# COMS0001_Beacon.net
KiCad netlist of a schematic drawn in Altium Designer
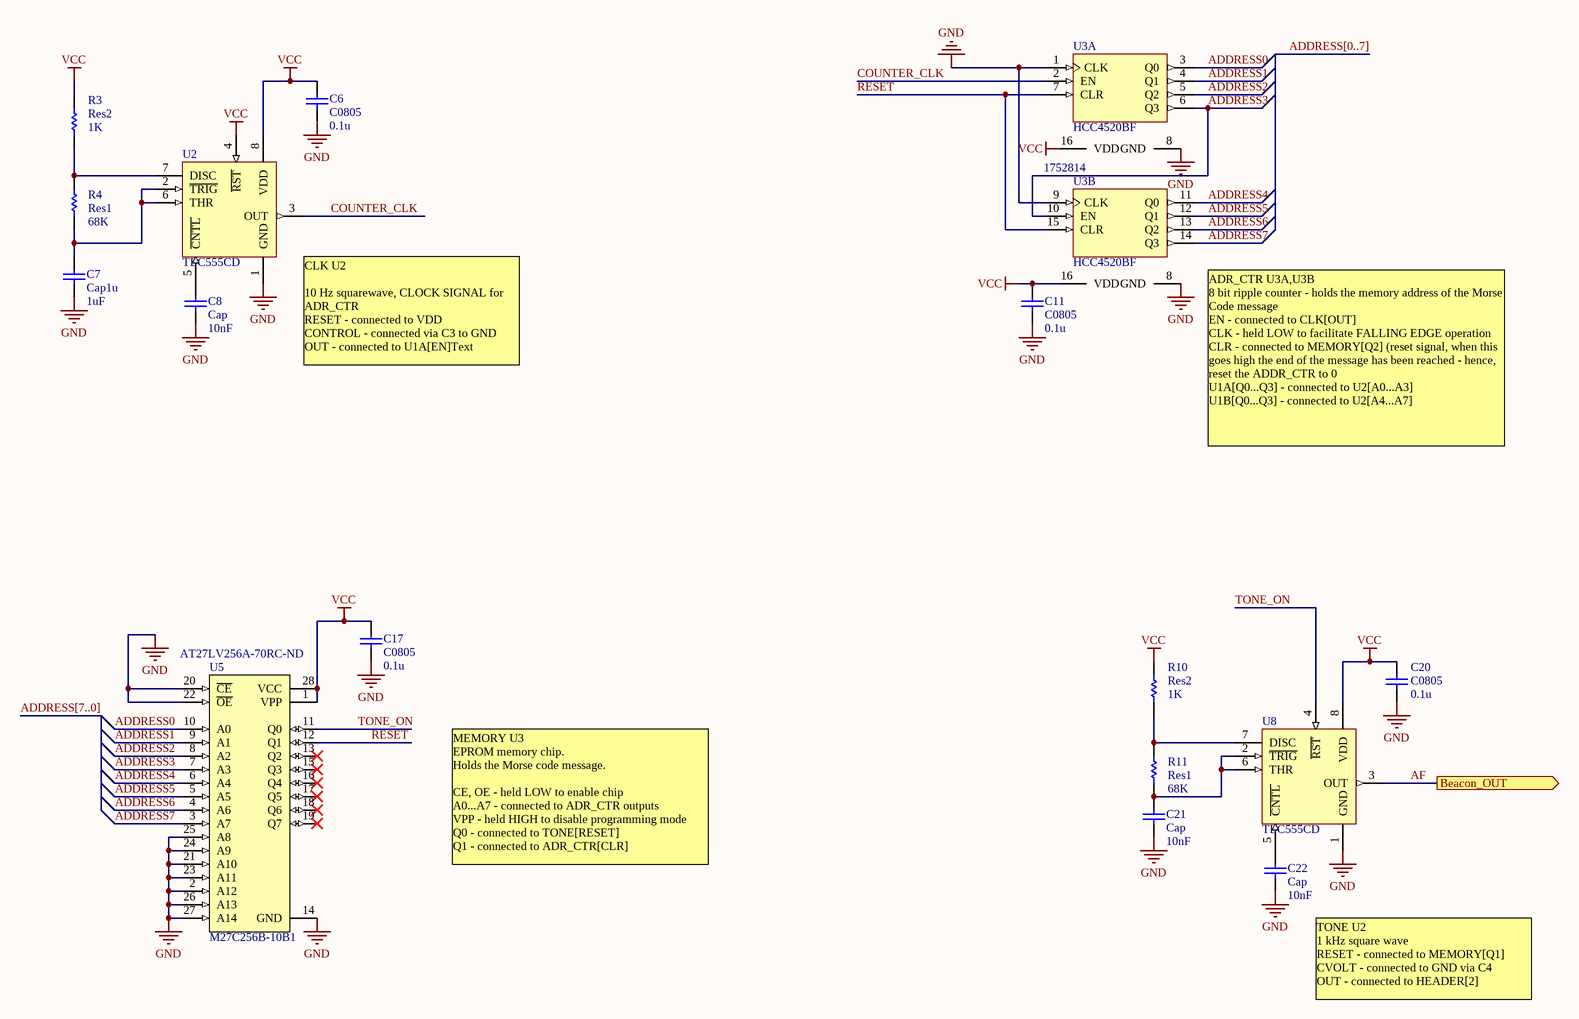
[diagram p0: COMS0001_Beacon.SchDoc]

(export (version "E")
  (design (tool "Eeschema 10.0.6"))
  (components
    (comp (ref "C6")
      (value "C0805")
      (footprint "CAPC2012M")
      (description "Capacitor")
      (fields (field (name "ALTIUM_VALUE") "0.1u") (field (name "PUBLISHER") "Altium Limited"))
      (libsource (lib "Miscellaneous Devices") (part "Cap"))
    )
    (comp (ref "C7")
      (value "Cap1u")
      (footprint "CAPC2012M")
      (description "Capacitor")
      (fields (field (name "ALTIUM_VALUE") "1uF") (field (name "PUBLISHER") "Altium Limited"))
      (libsource (lib "Miscellaneous Devices") (part "Cap"))
    )
    (comp (ref "C8")
      (value "Cap")
      (footprint "CAPC2012M")
      (description "Capacitor")
      (fields (field (name "ALTIUM_VALUE") "10nF") (field (name "PUBLISHER") "Altium Limited"))
      (libsource (lib "Miscellaneous Devices") (part "Cap"))
    )
    (comp (ref "C11")
      (value "C0805")
      (footprint "CAPC2012M")
      (description "Capacitor")
      (fields (field (name "ALTIUM_VALUE") "0.1u") (field (name "PUBLISHER") "Altium Limited"))
      (libsource (lib "Miscellaneous Devices") (part "Cap"))
    )
    (comp (ref "C17")
      (value "C0805")
      (footprint "CAPC2012M")
      (description "Capacitor")
      (fields (field (name "ALTIUM_VALUE") "0.1u") (field (name "PUBLISHER") "Altium Limited"))
      (libsource (lib "Miscellaneous Devices") (part "Cap"))
    )
    (comp (ref "C20")
      (value "C0805")
      (footprint "CAPC2012M")
      (description "Capacitor")
      (fields (field (name "ALTIUM_VALUE") "0.1u") (field (name "PUBLISHER") "Altium Limited"))
      (libsource (lib "Miscellaneous Devices") (part "Cap"))
    )
    (comp (ref "C21")
      (value "Cap")
      (footprint "CAPC2012M")
      (description "Capacitor")
      (fields (field (name "ALTIUM_VALUE") "10nF") (field (name "PUBLISHER") "Altium Limited"))
      (libsource (lib "Miscellaneous Devices") (part "Cap"))
    )
    (comp (ref "C22")
      (value "Cap")
      (footprint "CAPC2012M")
      (description "Capacitor")
      (fields (field (name "ALTIUM_VALUE") "10nF") (field (name "PUBLISHER") "Altium Limited"))
      (libsource (lib "Miscellaneous Devices") (part "Cap"))
    )
    (comp (ref "R3")
      (value "Res2")
      (footprint "RESC2012M")
      (description "Resistor")
      (fields (field (name "ALTIUM_VALUE") "1K") (field (name "PUBLISHER") "Altium Limited"))
      (libsource (lib "Miscellaneous Devices") (part "Res1"))
    )
    (comp (ref "R4")
      (value "Res1")
      (footprint "RESC2012M")
      (description "Resistor")
      (fields (field (name "ALTIUM_VALUE") "68K") (field (name "PUBLISHER") "Altium Limited"))
      (libsource (lib "Miscellaneous Devices") (part "Res1"))
    )
    (comp (ref "R10")
      (value "Res2")
      (footprint "RESC2012M")
      (description "Resistor")
      (fields (field (name "ALTIUM_VALUE") "1K") (field (name "PUBLISHER") "Altium Limited"))
      (libsource (lib "Miscellaneous Devices") (part "Res1"))
    )
    (comp (ref "R11")
      (value "Res1")
      (footprint "RESC2012M")
      (description "Resistor")
      (fields (field (name "ALTIUM_VALUE") "68K") (field (name "PUBLISHER") "Altium Limited"))
      (libsource (lib "Miscellaneous Devices") (part "Res1"))
    )
    (comp (ref "U2")
      (value "TLC555CD")
      (footprint "D008_M")
      (description "LinCMOS Timer")
      (fields (field (name "PUBLISHER") "Altium Limited"))
      (libsource (lib "TI Analog Timer Circuit") (part "TLC555CD"))
    )
    (comp (ref "U3")
      (value "HCC4520BF")
      (footprint "SOIC16_M")
      (description "Dual Binary Up-Counter")
      (fields (field (name "SUPPLIER PART NUMBER 1") "1752814") (field (name "PUBLISHER") "Altium Limited"))
      (libsource (lib "ST Logic Counter") (part "HCC4520BF"))
    )
    (comp (ref "U5")
      (value "M27C256B-10B1")
      (footprint "SOIC127P1199-28AM")
      (description "256 Kbit (32Kb X 8) UV EPROM and OTP EPROM")
      (fields
        (field (name "SUPPLIER PART NUMBER 1") "AT27LV256A-70RC-ND")
        (field (name "PUBLISHER") "Altium Limited")
      )
      (libsource (lib "ST Memory EPROM 16-512 Kbit") (part "M27C256B-10B1"))
    )
    (comp (ref "U8")
      (value "TLC555CD")
      (footprint "D008_M")
      (description "LinCMOS Timer")
      (fields (field (name "PUBLISHER") "Altium Limited"))
      (libsource (lib "TI Analog Timer Circuit") (part "TLC555CD"))
    )
  )
  (nets
    (net (code "1") (name "/ADDRESS0") (class "Default")
      (node (ref "U3") (pin "3") (pinfunction "Q0_3") (pintype "output"))
      (node (ref "U5") (pin "10") (pinfunction "A0_10") (pintype "input"))
    )
    (net (code "2") (name "/ADDRESS1") (class "Default")
      (node (ref "U3") (pin "4") (pinfunction "Q1_4") (pintype "output"))
      (node (ref "U5") (pin "9") (pinfunction "A1_9") (pintype "input"))
    )
    (net (code "3") (name "/ADDRESS2") (class "Default")
      (node (ref "U3") (pin "5") (pinfunction "Q2_5") (pintype "output"))
      (node (ref "U5") (pin "8") (pinfunction "A2_8") (pintype "input"))
    )
    (net (code "4") (name "/ADDRESS3") (class "Default")
      (node (ref "U3") (pin "10") (pinfunction "EN_10") (pintype "input"))
      (node (ref "U3") (pin "6") (pinfunction "Q3_6") (pintype "output"))
      (node (ref "U5") (pin "7") (pinfunction "A3_7") (pintype "input"))
    )
    (net (code "5") (name "/ADDRESS4") (class "Default")
      (node (ref "U3") (pin "11") (pinfunction "Q0_11") (pintype "output"))
      (node (ref "U5") (pin "6") (pinfunction "A4_6") (pintype "input"))
    )
    (net (code "6") (name "/ADDRESS5") (class "Default")
      (node (ref "U3") (pin "12") (pinfunction "Q1_12") (pintype "output"))
      (node (ref "U5") (pin "5") (pinfunction "A5_5") (pintype "input"))
    )
    (net (code "7") (name "/ADDRESS6") (class "Default")
      (node (ref "U3") (pin "13") (pinfunction "Q2_13") (pintype "output"))
      (node (ref "U5") (pin "4") (pinfunction "A6_4") (pintype "input"))
    )
    (net (code "8") (name "/ADDRESS7") (class "Default")
      (node (ref "U3") (pin "14") (pinfunction "Q3_14") (pintype "output"))
      (node (ref "U5") (pin "3") (pinfunction "A7_3") (pintype "input"))
    )
    (net (code "11") (name "/AF") (class "Default")
      (node (ref "U8") (pin "3") (pinfunction "OUT_3") (pintype "output"))
    )
    (net (code "12") (name "/COUNTER_CLK") (class "Default")
      (node (ref "U2") (pin "3") (pinfunction "OUT_3") (pintype "output"))
      (node (ref "U3") (pin "2") (pinfunction "EN_2") (pintype "input"))
    )
    (net (code "13") (name "/RESET") (class "Default")
      (node (ref "U3") (pin "15") (pinfunction "CLR_15") (pintype "input"))
      (node (ref "U3") (pin "7") (pinfunction "CLR_7") (pintype "input"))
      (node (ref "U5") (pin "12") (pinfunction "Q1_12") (pintype "bidirectional"))
    )
    (net (code "14") (name "/TONE_ON") (class "Default")
      (node (ref "U5") (pin "11") (pinfunction "Q0_11") (pintype "bidirectional"))
      (node (ref "U8") (pin "4") (pinfunction "~{RST}_4") (pintype "input"))
    )
    (net (code "15") (name "GND") (class "Default")
      (node (ref "C11") (pin "1") (pinfunction "1_1") (pintype "passive"))
      (node (ref "C17") (pin "1") (pinfunction "1_1") (pintype "passive"))
      (node (ref "C20") (pin "1") (pinfunction "1_1") (pintype "passive"))
      (node (ref "C21") (pin "1") (pinfunction "1_1") (pintype "passive"))
      (node (ref "C22") (pin "1") (pinfunction "1_1") (pintype "passive"))
      (node (ref "C6") (pin "1") (pinfunction "1_1") (pintype "passive"))
      (node (ref "C7") (pin "1") (pinfunction "1_1") (pintype "passive"))
      (node (ref "C8") (pin "1") (pinfunction "1_1") (pintype "passive"))
      (node (ref "U2") (pin "1") (pinfunction "GND_1") (pintype "power_in"))
      (node (ref "U3") (pin "1") (pinfunction "CLK_1") (pintype "input"))
      (node (ref "U3") (pin "8") (pinfunction "GND_8") (pintype "power_in"))
      (node (ref "U3") (pin "9") (pinfunction "CLK_9") (pintype "input"))
      (node (ref "U5") (pin "14") (pinfunction "GND_14") (pintype "power_in"))
      (node (ref "U5") (pin "2") (pinfunction "A12_2") (pintype "input"))
      (node (ref "U5") (pin "20") (pinfunction "~{CE}_20") (pintype "input"))
      (node (ref "U5") (pin "21") (pinfunction "A10_21") (pintype "input"))
      (node (ref "U5") (pin "22") (pinfunction "~{OE}_22") (pintype "input"))
      (node (ref "U5") (pin "23") (pinfunction "A11_23") (pintype "input"))
      (node (ref "U5") (pin "24") (pinfunction "A9_24") (pintype "input"))
      (node (ref "U5") (pin "25") (pinfunction "A8_25") (pintype "input"))
      (node (ref "U5") (pin "26") (pinfunction "A13_26") (pintype "input"))
      (node (ref "U5") (pin "27") (pinfunction "A14_27") (pintype "input"))
      (node (ref "U8") (pin "1") (pinfunction "GND_1") (pintype "power_in"))
    )
    (net (code "16") (name "Net-(U2-DISC)") (class "Default")
      (node (ref "R3") (pin "1") (pinfunction "1_1") (pintype "passive"))
      (node (ref "R4") (pin "2") (pinfunction "2_2") (pintype "passive"))
      (node (ref "U2") (pin "7") (pinfunction "DISC_7") (pintype "open_collector"))
    )
    (net (code "17") (name "Net-(U2-THR)") (class "Default")
      (node (ref "C7") (pin "2") (pinfunction "2_2") (pintype "passive"))
      (node (ref "R4") (pin "1") (pinfunction "1_1") (pintype "passive"))
      (node (ref "U2") (pin "2") (pinfunction "~{TRIG}_2") (pintype "input"))
      (node (ref "U2") (pin "6") (pinfunction "THR_6") (pintype "input"))
    )
    (net (code "18") (name "Net-(U2-~{CNTL})") (class "Default")
      (node (ref "C8") (pin "2") (pinfunction "2_2") (pintype "passive"))
      (node (ref "U2") (pin "5") (pinfunction "~{CNTL}_5") (pintype "input"))
    )
    (net (code "19") (name "Net-(U8-DISC)") (class "Default")
      (node (ref "R10") (pin "1") (pinfunction "1_1") (pintype "passive"))
      (node (ref "R11") (pin "2") (pinfunction "2_2") (pintype "passive"))
      (node (ref "U8") (pin "7") (pinfunction "DISC_7") (pintype "open_collector"))
    )
    (net (code "20") (name "Net-(U8-THR)") (class "Default")
      (node (ref "C21") (pin "2") (pinfunction "2_2") (pintype "passive"))
      (node (ref "R11") (pin "1") (pinfunction "1_1") (pintype "passive"))
      (node (ref "U8") (pin "2") (pinfunction "~{TRIG}_2") (pintype "input"))
      (node (ref "U8") (pin "6") (pinfunction "THR_6") (pintype "input"))
    )
    (net (code "21") (name "Net-(U8-~{CNTL})") (class "Default")
      (node (ref "C22") (pin "2") (pinfunction "2_2") (pintype "passive"))
      (node (ref "U8") (pin "5") (pinfunction "~{CNTL}_5") (pintype "input"))
    )
    (net (code "22") (name "VCC") (class "Default")
      (node (ref "C11") (pin "2") (pinfunction "2_2") (pintype "passive"))
      (node (ref "C17") (pin "2") (pinfunction "2_2") (pintype "passive"))
      (node (ref "C20") (pin "2") (pinfunction "2_2") (pintype "passive"))
      (node (ref "C6") (pin "2") (pinfunction "2_2") (pintype "passive"))
      (node (ref "R10") (pin "2") (pinfunction "2_2") (pintype "passive"))
      (node (ref "R3") (pin "2") (pinfunction "2_2") (pintype "passive"))
      (node (ref "U2") (pin "4") (pinfunction "~{RST}_4") (pintype "input"))
      (node (ref "U2") (pin "8") (pinfunction "VDD_8") (pintype "power_in"))
      (node (ref "U3") (pin "16") (pinfunction "VDD_16") (pintype "power_in"))
      (node (ref "U5") (pin "1") (pinfunction "VPP_1") (pintype "power_in"))
      (node (ref "U5") (pin "28") (pinfunction "VCC_28") (pintype "power_in"))
      (node (ref "U8") (pin "8") (pinfunction "VDD_8") (pintype "power_in"))
    )
    (net (code "23") (name "unconnected-(U5-Q2-Pad13)") (class "Default")
      (node (ref "U5") (pin "13") (pinfunction "Q2_13") (pintype "bidirectional+no_connect"))
    )
    (net (code "24") (name "unconnected-(U5-Q3-Pad15)") (class "Default")
      (node (ref "U5") (pin "15") (pinfunction "Q3_15") (pintype "bidirectional+no_connect"))
    )
    (net (code "25") (name "unconnected-(U5-Q4-Pad16)") (class "Default")
      (node (ref "U5") (pin "16") (pinfunction "Q4_16") (pintype "bidirectional+no_connect"))
    )
    (net (code "26") (name "unconnected-(U5-Q5-Pad17)") (class "Default")
      (node (ref "U5") (pin "17") (pinfunction "Q5_17") (pintype "bidirectional+no_connect"))
    )
    (net (code "27") (name "unconnected-(U5-Q6-Pad18)") (class "Default")
      (node (ref "U5") (pin "18") (pinfunction "Q6_18") (pintype "bidirectional+no_connect"))
    )
    (net (code "28") (name "unconnected-(U5-Q7-Pad19)") (class "Default")
      (node (ref "U5") (pin "19") (pinfunction "Q7_19") (pintype "bidirectional+no_connect"))
    )
  )
)
